# voltage_doubler.net
KiCad netlist of a schematic drawn in EAGLE
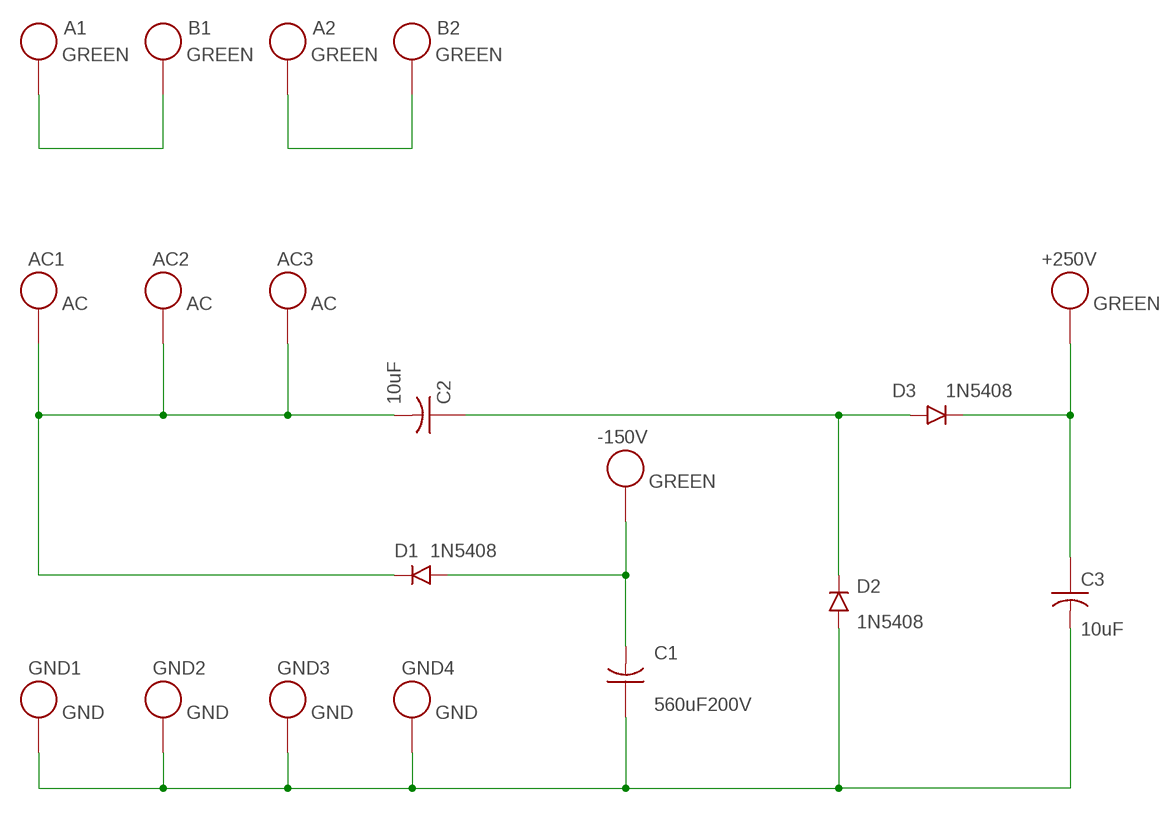
[diagram p0: schematic, sheet 1]

(export (version "E")
  (design (tool "Eeschema 10.0.6"))
  (components
    (comp (ref "+250V")
      (value "GREEN")
      (footprint "eagle-import:AWG22")
      (fields (field (name "MPN") "108-0904-001"))
      (libsource (lib "eagle-import") (part "BANANA_JACK_GREEN"))
    )
    (comp (ref "-150V")
      (value "GREEN")
      (footprint "eagle-import:AWG22")
      (fields (field (name "MPN") "108-0904-001"))
      (libsource (lib "eagle-import") (part "BANANA_JACK_GREEN"))
    )
    (comp (ref "A1")
      (value "GREEN")
      (footprint "eagle-import:AWG22")
      (fields (field (name "MPN") "108-0904-001"))
      (libsource (lib "eagle-import") (part "BANANA_JACK_GREEN"))
    )
    (comp (ref "A2")
      (value "GREEN")
      (footprint "eagle-import:AWG22")
      (fields (field (name "MPN") "108-0904-001"))
      (libsource (lib "eagle-import") (part "BANANA_JACK_GREEN"))
    )
    (comp (ref "AC1")
      (value "AC")
      (footprint "eagle-import:AWG22")
      (fields (field (name "MPN") "108-0904-001"))
      (libsource (lib "eagle-import") (part "BANANA_JACK_GREEN"))
    )
    (comp (ref "AC2")
      (value "AC")
      (footprint "eagle-import:AWG22")
      (fields (field (name "MPN") "108-0904-001"))
      (libsource (lib "eagle-import") (part "BANANA_JACK_GREEN"))
    )
    (comp (ref "AC3")
      (value "AC")
      (footprint "eagle-import:AWG22")
      (fields (field (name "MPN") "108-0904-001"))
      (libsource (lib "eagle-import") (part "BANANA_JACK_GREEN"))
    )
    (comp (ref "B1")
      (value "GREEN")
      (footprint "eagle-import:AWG22")
      (fields (field (name "MPN") "108-0904-001"))
      (libsource (lib "eagle-import") (part "BANANA_JACK_GREEN"))
    )
    (comp (ref "B2")
      (value "GREEN")
      (footprint "eagle-import:AWG22")
      (fields (field (name "MPN") "108-0904-001"))
      (libsource (lib "eagle-import") (part "BANANA_JACK_GREEN"))
    )
    (comp (ref "C1")
      (value "560uF200V")
      (footprint "eagle-import:WIREDCAP")
      (libsource (lib "eagle-import") (part "WIREDCAP"))
    )
    (comp (ref "C2")
      (value "10uF")
      (footprint "eagle-import:AXIAL10UF400V")
      (libsource (lib "eagle-import") (part "CAP400V10UF"))
    )
    (comp (ref "C3")
      (value "10uF")
      (footprint "eagle-import:AXIAL10UF400V")
      (libsource (lib "eagle-import") (part "CAP400V10UF"))
    )
    (comp (ref "D1")
      (value "1N5408")
      (footprint "eagle-import:DO-201AD")
      (libsource (lib "eagle-import") (part "1N5408"))
    )
    (comp (ref "D2")
      (value "1N5408")
      (footprint "eagle-import:DO-201AD")
      (libsource (lib "eagle-import") (part "1N5408"))
    )
    (comp (ref "D3")
      (value "1N5408")
      (footprint "eagle-import:DO-201AD")
      (libsource (lib "eagle-import") (part "1N5408"))
    )
    (comp (ref "GND1")
      (value "GND")
      (footprint "eagle-import:AWG22")
      (fields (field (name "MPN") "108-0904-001"))
      (libsource (lib "eagle-import") (part "BANANA_JACK_GREEN"))
    )
    (comp (ref "GND2")
      (value "GND")
      (footprint "eagle-import:AWG22")
      (fields (field (name "MPN") "108-0904-001"))
      (libsource (lib "eagle-import") (part "BANANA_JACK_GREEN"))
    )
    (comp (ref "GND3")
      (value "GND")
      (footprint "eagle-import:AWG22")
      (fields (field (name "MPN") "108-0904-001"))
      (libsource (lib "eagle-import") (part "BANANA_JACK_GREEN"))
    )
    (comp (ref "GND4")
      (value "GND")
      (footprint "eagle-import:AWG22")
      (fields (field (name "MPN") "108-0904-001"))
      (libsource (lib "eagle-import") (part "BANANA_JACK_GREEN"))
    )
  )
  (nets
    (net (code "1") (name "Net-(A1-PadP$1)") (class "Default")
      (node (ref "A1") (pin "P$1") (pinfunction "P$1_P$1") (pintype "bidirectional"))
      (node (ref "B1") (pin "P$1") (pinfunction "P$1_P$1") (pintype "bidirectional"))
    )
    (net (code "2") (name "Net-(A2-PadP$1)") (class "Default")
      (node (ref "A2") (pin "P$1") (pinfunction "P$1_P$1") (pintype "bidirectional"))
      (node (ref "B2") (pin "P$1") (pinfunction "P$1_P$1") (pintype "bidirectional"))
    )
    (net (code "3") (name "Net-(C1-1)") (class "Default")
      (node (ref "C1") (pin "P$1") (pinfunction "1_P$1") (pintype "passive"))
      (node (ref "C3") (pin "P$2") (pinfunction "2_P$2") (pintype "passive"))
      (node (ref "D2") (pin "A") (pinfunction "A_A") (pintype "passive"))
      (node (ref "GND1") (pin "P$1") (pinfunction "P$1_P$1") (pintype "bidirectional"))
      (node (ref "GND2") (pin "P$1") (pinfunction "P$1_P$1") (pintype "bidirectional"))
      (node (ref "GND3") (pin "P$1") (pinfunction "P$1_P$1") (pintype "bidirectional"))
      (node (ref "GND4") (pin "P$1") (pinfunction "P$1_P$1") (pintype "bidirectional"))
    )
    (net (code "4") (name "Net-(C1-2)") (class "Default")
      (node (ref "-150V") (pin "P$1") (pinfunction "P$1_P$1") (pintype "bidirectional"))
      (node (ref "C1") (pin "P$2") (pinfunction "2_P$2") (pintype "passive"))
      (node (ref "D1") (pin "A") (pinfunction "A_A") (pintype "passive"))
    )
    (net (code "5") (name "Net-(C2-1)") (class "Default")
      (node (ref "C2") (pin "P$1") (pinfunction "1_P$1") (pintype "passive"))
      (node (ref "D2") (pin "C") (pinfunction "C_C") (pintype "passive"))
      (node (ref "D3") (pin "A") (pinfunction "A_A") (pintype "passive"))
    )
    (net (code "6") (name "Net-(C2-2)") (class "Default")
      (node (ref "AC1") (pin "P$1") (pinfunction "P$1_P$1") (pintype "bidirectional"))
      (node (ref "AC2") (pin "P$1") (pinfunction "P$1_P$1") (pintype "bidirectional"))
      (node (ref "AC3") (pin "P$1") (pinfunction "P$1_P$1") (pintype "bidirectional"))
      (node (ref "C2") (pin "P$2") (pinfunction "2_P$2") (pintype "passive"))
      (node (ref "D1") (pin "C") (pinfunction "C_C") (pintype "passive"))
    )
    (net (code "7") (name "Net-(C3-1)") (class "Default")
      (node (ref "+250V") (pin "P$1") (pinfunction "P$1_P$1") (pintype "bidirectional"))
      (node (ref "C3") (pin "P$1") (pinfunction "1_P$1") (pintype "passive"))
      (node (ref "D3") (pin "C") (pinfunction "C_C") (pintype "passive"))
    )
  )
)
